# BPBE_Module.net
KiCad netlist of a schematic drawn in Altium Designer
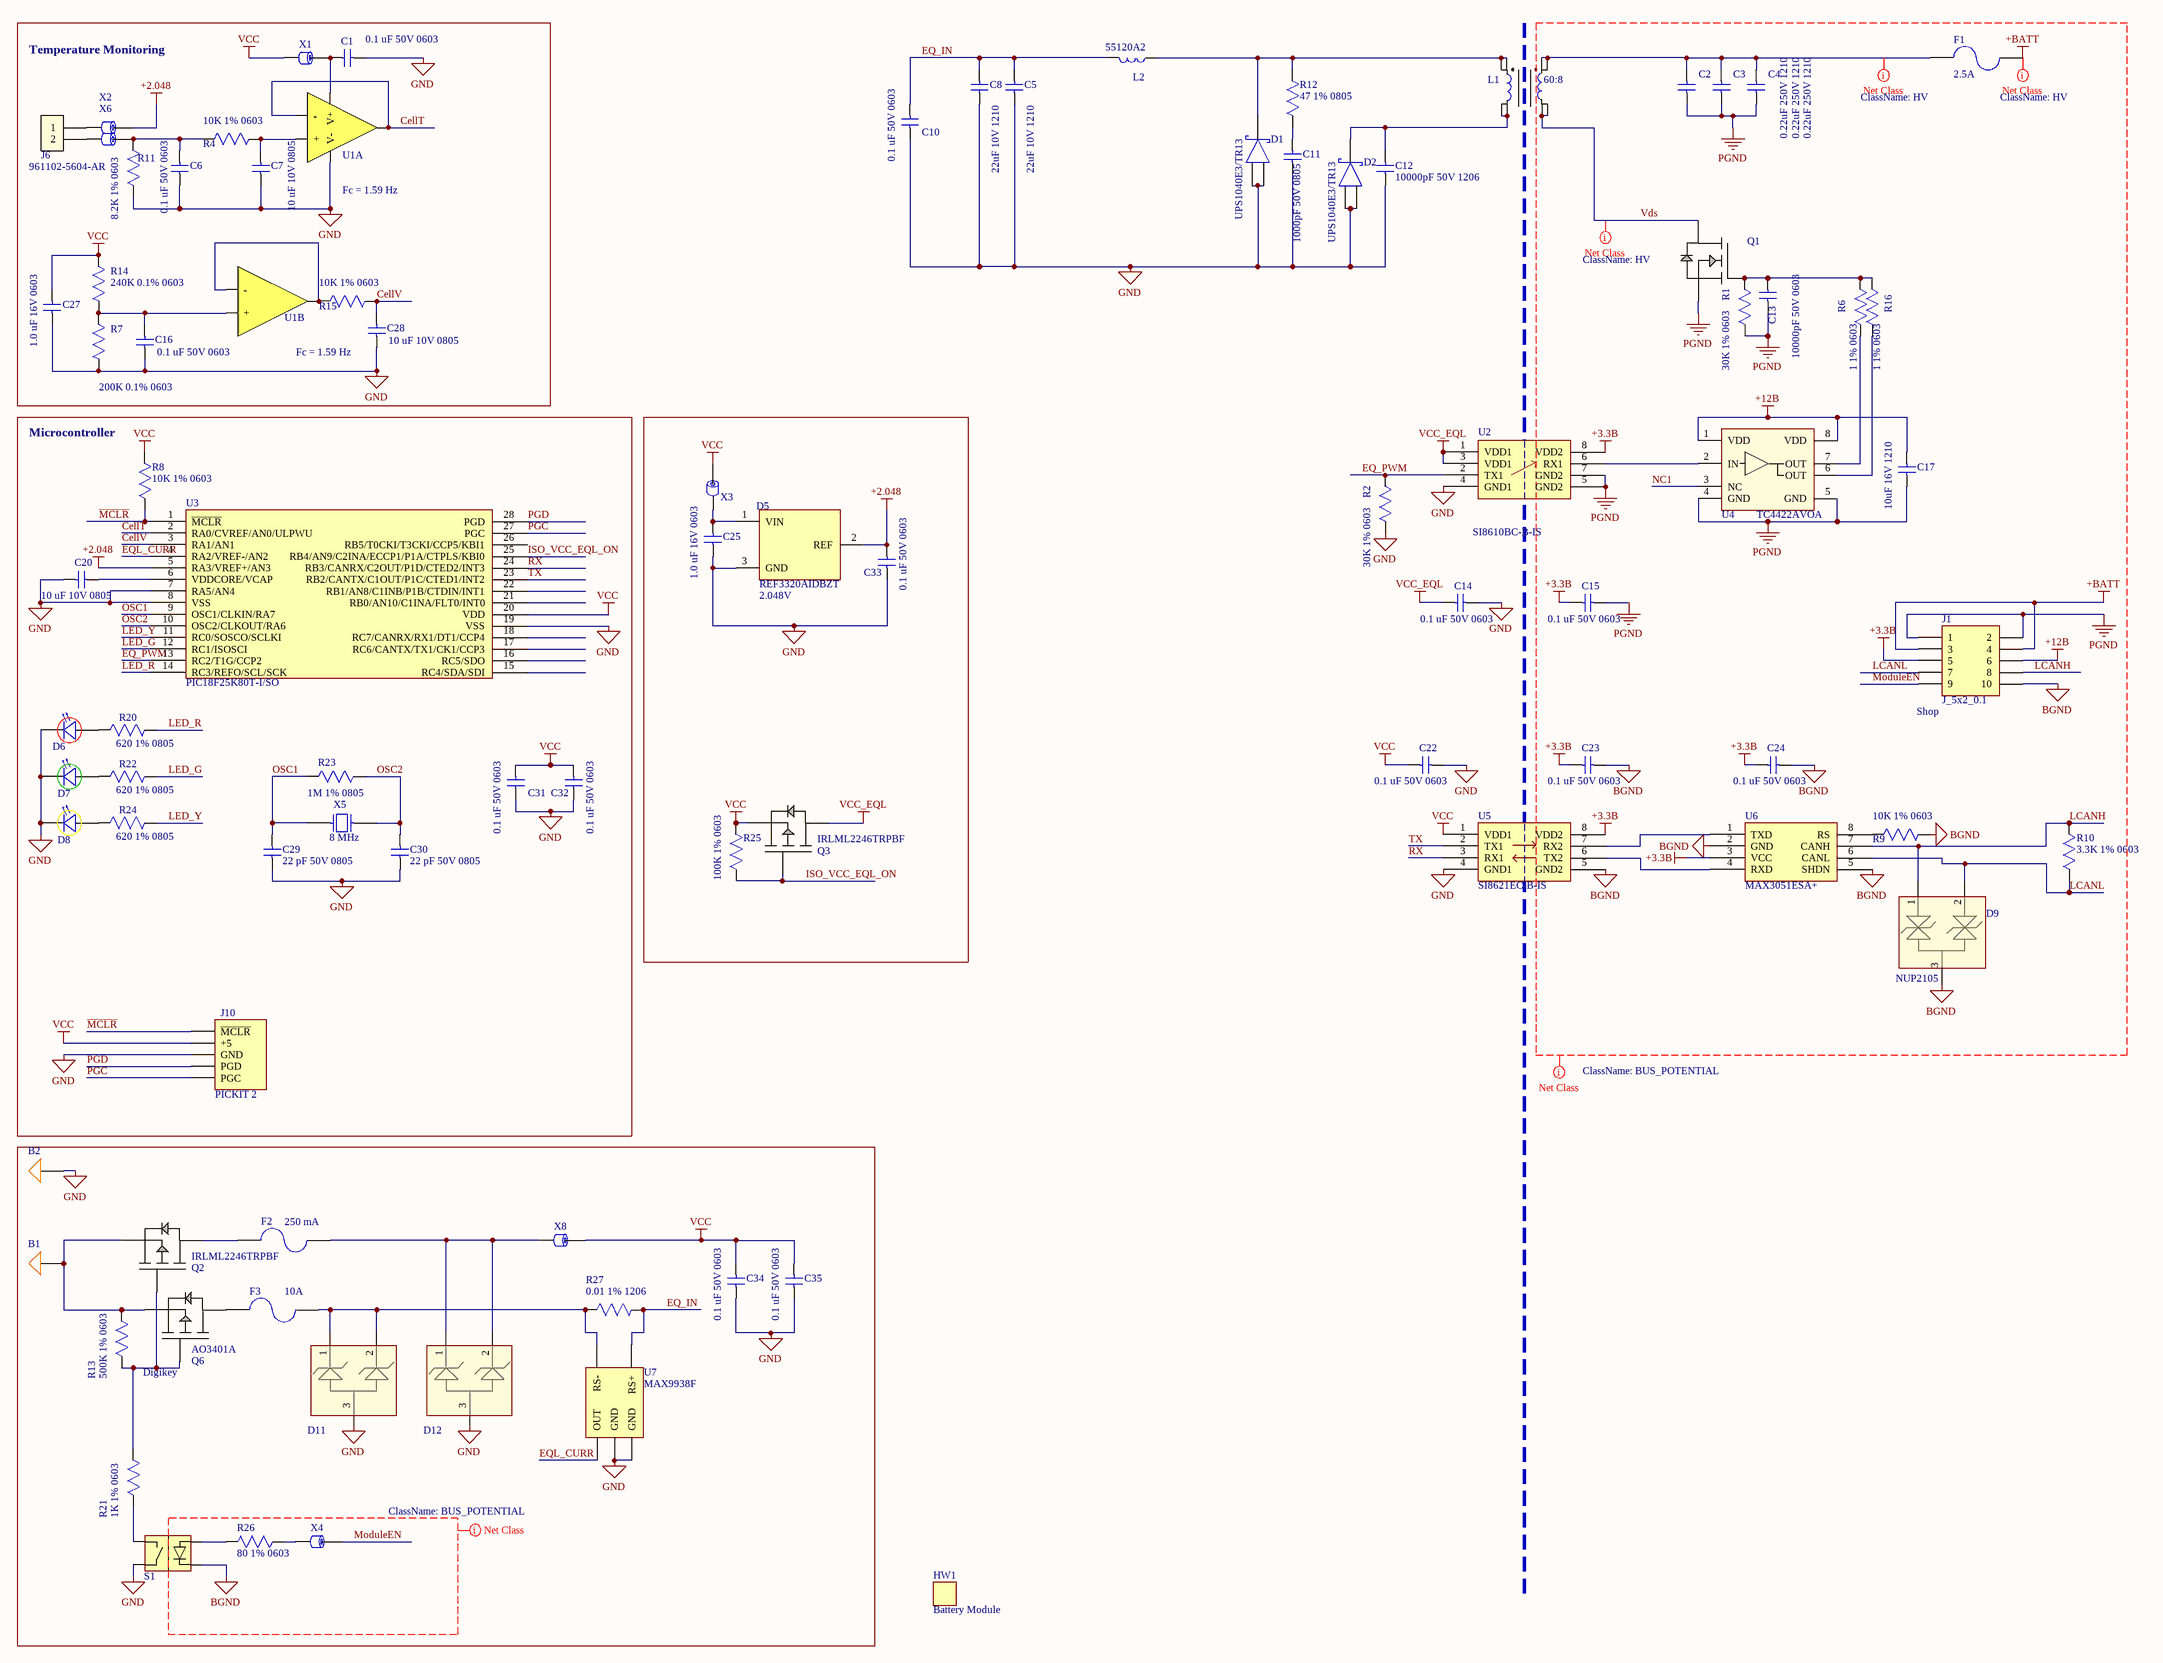
[diagram p0: BPBE Module.SchDoc]

(export (version "E")
  (design (tool "Eeschema 10.0.6"))
  (components
    (comp (ref "B1")
      (value "J_C3_BATTERY_PAD")
      (footprint "BatteryPad")
      (libsource (lib "c3_SchLib") (part "J_C3_BATTERY_PAD"))
    )
    (comp (ref "B2")
      (value "J_C3_BATTERY_PAD")
      (footprint "BatteryPad")
      (libsource (lib "c3_SchLib") (part "J_C3_BATTERY_PAD"))
    )
    (comp (ref "C1")
      (value "0.1 uF 50V 0603")
      (footprint "0603_cap")
      (description "CAP CER 0.1UF 50V 10% X7R 0603")
      (fields (field (name "MANUFACTURER") "Yaego") (field (name "Comment") "CAP 0603"))
      (libsource (lib "Nutz") (part "C_0603"))
    )
    (comp (ref "C2")
      (value "0.22uF 250V 1210")
      (footprint "1210_Capacitor")
      (description "CAP CER 0.22UF 250V 20% X7R 1210")
      (fields (field (name "MANUFACTURER") "TDK Corporation") (field (name "Comment") "CAP 1210"))
      (libsource (lib "c3_SchLib") (part "C_1210"))
    )
    (comp (ref "C3")
      (value "0.22uF 250V 1210")
      (footprint "1210_Capacitor")
      (description "CAP CER 0.22UF 250V 20% X7R 1210")
      (fields (field (name "MANUFACTURER") "TDK Corporation"))
      (libsource (lib "c3_SchLib") (part "C_1210"))
    )
    (comp (ref "C4")
      (value "0.22uF 250V 1210")
      (footprint "1210_Capacitor")
      (description "CAP CER 0.22UF 250V 20% X7R 1210")
      (fields (field (name "MANUFACTURER") "TDK Corporation") (field (name "Comment") "CAP 1210"))
      (libsource (lib "c3_SchLib") (part "C_1210"))
    )
    (comp (ref "C5")
      (value "22uF 10V 1210")
      (footprint "1210_Capacitor")
      (description "CAP CER 22UF 10V 10% X7R 1210")
      (fields (field (name "MANUFACTURER") "TDK Corporation") (field (name "Comment") "CAP 1210"))
      (libsource (lib "c3_SchLib") (part "C_1210"))
    )
    (comp (ref "C6")
      (value "0.1 uF 50V 0603")
      (footprint "0603_cap")
      (description "CAP CER 0.1UF 50V 10% X7R 0603")
      (fields (field (name "MANUFACTURER") "Yaego") (field (name "Comment") "CAP 0603"))
      (libsource (lib "Nutz") (part "C_0603"))
    )
    (comp (ref "C7")
      (value "10 uF 10V 0805")
      (footprint "0805_Capacitor")
      (description "CAP CER 10UF 10V 10% X5R 0805")
      (fields (field (name "MANUFACTURER") "Taiyo Yuden") (field (name "Comment") "CAP 0805"))
      (libsource (lib "Nutz") (part "C_0805"))
    )
    (comp (ref "C8")
      (value "22uF 10V 1210")
      (footprint "1210_Capacitor")
      (description "CAP CER 22UF 10V 10% X7R 1210")
      (fields (field (name "MANUFACTURER") "TDK Corporation") (field (name "Comment") "CAP 1210"))
      (libsource (lib "c3_SchLib") (part "C_1210"))
    )
    (comp (ref "C10")
      (value "0.1 uF 50V 0603")
      (footprint "0603_cap")
      (description "CAP CER 0.1UF 50V 10% X7R 0603")
      (fields (field (name "MANUFACTURER") "Yaego") (field (name "Comment") "CAP 0603"))
      (libsource (lib "Nutz") (part "C_0603"))
    )
    (comp (ref "C11")
      (value "1000pF 50V 0805")
      (footprint "0805_Capacitor")
      (description "CAP CER 1000PF 50V 10% NP0 0805")
      (fields (field (name "MANUFACTURER") "Johanson Dielectrics Inc") (field (name "Comment") "CAP 1000pF"))
      (libsource (lib "c3_SchLib") (part "C_0805_1000pF"))
    )
    (comp (ref "C12")
      (value "10000pF 50V 1206")
      (footprint "1206_CAPACITOR")
      (description "CAP CERM 1206")
      (fields (field (name "Comment") "CAP 1206"))
      (libsource (lib "Nutz") (part "C_1206"))
    )
    (comp (ref "C13")
      (value "10000pF 50V 0603")
      (footprint "0603_cap")
      (description "CAP CER 10000PF 50V 10% X7R 0603")
      (fields (field (name "MANUFACTURER") "Yageo") (field (name "Comment") "CAP 0603"))
      (libsource (lib "Nutz") (part "C_0603"))
    )
    (comp (ref "C14")
      (value "0.1 uF 50V 0603")
      (footprint "0603_cap")
      (description "CAP CER 0.1UF 50V 10% X7R 0603")
      (fields (field (name "MANUFACTURER") "Yaego") (field (name "Comment") "CAP 0603"))
      (libsource (lib "Nutz") (part "C_0603"))
    )
    (comp (ref "C15")
      (value "0.1 uF 50V 0603")
      (footprint "0603_cap")
      (description "CAP CER 0.1UF 50V 10% X7R 0603")
      (fields (field (name "MANUFACTURER") "Yaego") (field (name "Comment") "CAP 0603"))
      (libsource (lib "Nutz") (part "C_0603"))
    )
    (comp (ref "C16")
      (value "0.1 uF 50V 0603")
      (footprint "0603_cap")
      (description "CAP CER 0.1UF 50V 10% X7R 0603")
      (fields (field (name "MANUFACTURER") "Yaego") (field (name "Comment") "CAP 0603"))
      (libsource (lib "Nutz") (part "C_0603"))
    )
    (comp (ref "C17")
      (value "10uF 16V 1210")
      (footprint "1210_Capacitor")
      (description "CAP CER 10UF 16V 10% X5R 1210")
      (fields (field (name "MANUFACTURER") "Taiyo Yuden") (field (name "Comment") "CAP 1210"))
      (libsource (lib "c3_SchLib") (part "C_1210"))
    )
    (comp (ref "C20")
      (value "10 uF 10V 0805")
      (footprint "0805_Capacitor")
      (description "CAP CER 10UF 10V 10% X5R 0805")
      (fields (field (name "MANUFACTURER") "Taiyo Yuden") (field (name "Comment") "CAP 0805"))
      (libsource (lib "Nutz") (part "C_0805"))
    )
    (comp (ref "C22")
      (value "0.1 uF 50V 0603")
      (footprint "0603_cap")
      (description "CAP CER 0.1UF 50V 10% X7R 0603")
      (fields (field (name "MANUFACTURER") "Yaego") (field (name "Comment") "CAP 0603"))
      (libsource (lib "Nutz") (part "C_0603"))
    )
    (comp (ref "C23")
      (value "0.1 uF 50V 0603")
      (footprint "0603_cap")
      (description "CAP CER 0.1UF 50V 10% X7R 0603")
      (fields (field (name "MANUFACTURER") "Yaego") (field (name "Comment") "CAP 0603"))
      (libsource (lib "Nutz") (part "C_0603"))
    )
    (comp (ref "C24")
      (value "0.1 uF 50V 0603")
      (footprint "0603_cap")
      (description "CAP CER 0.1UF 50V 10% X7R 0603")
      (fields (field (name "MANUFACTURER") "Yaego") (field (name "Comment") "CAP 0603"))
      (libsource (lib "Nutz") (part "C_0603"))
    )
    (comp (ref "C25")
      (value "1.0 uF 16V 0603")
      (footprint "0603_cap")
      (description "CAP CER 1UF 16V 10% X7R 0603")
      (fields (field (name "MANUFACTURER") "Taiyo Yuden") (field (name "Comment") "CAP 0603"))
      (libsource (lib "Nutz") (part "C_0603"))
    )
    (comp (ref "C27")
      (value "1.0 uF 16V 0603")
      (footprint "0603_cap")
      (description "CAP CER 1UF 16V 10% X7R 0603")
      (fields (field (name "MANUFACTURER") "Taiyo Yuden") (field (name "Comment") "CAP 0603"))
      (libsource (lib "Nutz") (part "C_0603"))
    )
    (comp (ref "C28")
      (value "10 uF 10V 0805")
      (footprint "0805_Capacitor")
      (description "CAP CER 10UF 10V 10% X5R 0805")
      (fields (field (name "MANUFACTURER") "Taiyo Yuden") (field (name "Comment") "CAP 0805"))
      (libsource (lib "Nutz") (part "C_0805"))
    )
    (comp (ref "C29")
      (value "22 pF 50V 0805")
      (footprint "0805_Capacitor")
      (description "CAP CER 22PF 50V 5% NP0 0805")
      (fields (field (name "MANUFACTURER") "Johanson Dielectrics Inc") (field (name "Comment") "CAP 0805"))
      (libsource (lib "Nutz") (part "C_0805"))
    )
    (comp (ref "C30")
      (value "22 pF 50V 0805")
      (footprint "0805_Capacitor")
      (description "CAP CER 22PF 50V 5% NP0 0805")
      (fields (field (name "MANUFACTURER") "Johanson Dielectrics Inc") (field (name "Comment") "CAP 0805"))
      (libsource (lib "Nutz") (part "C_0805"))
    )
    (comp (ref "C31")
      (value "0.1 uF 50V 0603")
      (footprint "0603_cap")
      (description "CAP CER 0.1UF 50V 10% X7R 0603")
      (fields (field (name "MANUFACTURER") "Yaego") (field (name "Comment") "CAP 0603"))
      (libsource (lib "Nutz") (part "C_0603"))
    )
    (comp (ref "C32")
      (value "0.1 uF 50V 0603")
      (footprint "0603_cap")
      (description "CAP CER 0.1UF 50V 10% X7R 0603")
      (fields (field (name "MANUFACTURER") "Yaego") (field (name "Comment") "CAP 0603"))
      (libsource (lib "Nutz") (part "C_0603"))
    )
    (comp (ref "C33")
      (value "0.1 uF 50V 0603")
      (footprint "0603_cap")
      (description "CAP CER 0.1UF 50V 10% X7R 0603")
      (fields (field (name "MANUFACTURER") "Yaego") (field (name "Comment") "CAP 0603"))
      (libsource (lib "Nutz") (part "C_0603"))
    )
    (comp (ref "C34")
      (value "0.1 uF 50V 0603")
      (footprint "0603_cap")
      (description "CAP CER 0.1UF 50V 10% X7R 0603")
      (fields (field (name "MANUFACTURER") "Yaego") (field (name "Comment") "CAP 0603"))
      (libsource (lib "Nutz") (part "C_0603"))
    )
    (comp (ref "C35")
      (value "0.1 uF 50V 0603")
      (footprint "0603_cap")
      (description "CAP CER 0.1UF 50V 10% X7R 0603")
      (fields (field (name "MANUFACTURER") "Yaego") (field (name "Comment") "CAP 0603"))
      (libsource (lib "Nutz") (part "C_0603"))
    )
    (comp (ref "D1")
      (value "UPS1040E3/TR13")
      (footprint "TO-277")
      (description "DIODE SCHOTTKY 10A 40V PWRMITE3")
      (fields (field (name "MANUFACTURER") "Microsemi") (field (name "MANUFACTURER PN") "UPS1040E3/TR13"))
      (libsource (lib "c3_SchLib") (part "D_UPS1040E3/TR13"))
    )
    (comp (ref "D2")
      (value "UPS1040E3/TR13")
      (footprint "TO-277")
      (description "DIODE SCHOTTKY 10A 40V PWRMITE3")
      (fields (field (name "MANUFACTURER") "Microsemi") (field (name "MANUFACTURER PN") "UPS1040E3/TR13"))
      (libsource (lib "c3_SchLib") (part "D_UPS1040E3/TR13"))
    )
    (comp (ref "D5")
      (value "2.048V")
      (footprint "SOT-23")
      (description "IC LDO V-REF 2.048V SOT23-3")
      (fields (field (name "MANUFACTURER") "TI") (field (name "MANUFACTURER PN") "REF3320AIDBZT"))
      (libsource (lib "c3_SchLib") (part "D_REF3320AIDBZT"))
    )
    (comp (ref "D6")
      (value "D_LED_0805_RED")
      (footprint "0805P_RED")
      (description "LED 2X1.2MM 625NM RD WTR CLR SMD 0805")
      (fields (field (name "MANUFACTURER") "Kingbright Corp"))
      (libsource (lib "c3_SchLib") (part "D_LED_0805_RED"))
    )
    (comp (ref "D7")
      (value "D_LED_0805_GREEN")
      (footprint "0805P_Green")
      (description "LED 2X1.2MM 568NM GN WTR CLR SMD 0805")
      (fields (field (name "MANUFACTURER") "Kingbright Corp"))
      (libsource (lib "c3_SchLib") (part "D_LED_0805_GREEN"))
    )
    (comp (ref "D8")
      (value "D_LED_0805_YELLOW")
      (footprint "0805P_YELLOW")
      (description "LED 2X1.2MM 588NM YW WTR CLR SMD 0805")
      (fields (field (name "MANUFACTURER") "Kingbright Corp"))
      (libsource (lib "c3_SchLib") (part "D_LED_0805_YELLOW"))
    )
    (comp (ref "D9")
      (value "CAN TVS")
      (footprint "SOT-23")
      (description "IC CAN BUS PROTECTOR DUAL SOT23")
      (fields (field (name "MANUFACTURER") "ON Semiconductor") (field (name "MANUFACTURER PN") "NUP2105"))
      (libsource (lib "c3_SchLib") (part "D_NUP2105"))
    )
    (comp (ref "D11")
      (value "MMBZ6V8AL,215")
      (footprint "SOT-23")
      (description "DIODE ESD PROT DBL 4.5V SOT23")
      (fields (field (name "MANUFACTURER") "NXP"))
      (libsource (lib "c3_SchLib") (part "D_MMBZ6V8AL,215"))
    )
    (comp (ref "D12")
      (value "MMBZ6V8AL,215")
      (footprint "SOT-23")
      (description "DIODE ESD PROT DBL 4.5V SOT23")
      (fields (field (name "MANUFACTURER") "NXP"))
      (libsource (lib "c3_SchLib") (part "D_MMBZ6V8AL,215"))
    )
    (comp (ref "F1")
      (value "2.5A")
      (footprint "2410")
      (description "FUSE 2.5A 125V FAST 2410")
      (fields (field (name "MANUFACTURER") "TE Connectivity") (field (name "Comment") "F_SSQ 12"))
      (libsource (lib "c3_SchLib") (part "F_SSQ 12"))
    )
    (comp (ref "F2")
      (value "250 mA")
      (footprint "1206_RESISTOR")
      (description "FUSE 250MA 125V 1206 FAST C1Q")
      (fields (field (name "MANUFACTURER") "Bel Fuse Inc"))
      (libsource (lib "c3_SchLib") (part "F_250mA_1206"))
    )
    (comp (ref "F3")
      (value "10A")
      (footprint "2410")
      (description "FUSE 10A 125V 6125 FAST SSQ")
      (fields (field (name "MANUFACTURER") "Bel Fuse Inc") (field (name "Comment") "F_SSQ 10"))
      (libsource (lib "c3_SchLib") (part "F_SSQ 12"))
    )
    (comp (ref "HW1")
      (value "Battery Module")
      (footprint "Battery Module")
      (libsource (lib "c3_SchLib") (part "Battery Module"))
    )
    (comp (ref "J1")
      (value "J_5x2_0.1")
      (footprint "10PIN_2_.100IN")
      (description "5 x 2 0.1\" Header")
      (fields (field (name "DISTRIBUTOR") "Shop"))
      (libsource (lib "Nutz") (part "J_5x2_0.1"))
    )
    (comp (ref "J6")
      (value "J_Thermistor_Connector")
      (footprint "SIP_HEADER_2")
      (description "Thermistor Connector")
      (fields (field (name "MANUFACTURER PN") "961102-5604-AR") (field (name "MANUFACTURER") "3M"))
      (libsource (lib "c3_SchLib") (part "J_Thermistor_Connector"))
    )
    (comp (ref "J10")
      (value "PICKIT 2")
      (footprint "CONN FEMALE 5POS .100\" R/A GOLD")
      (description "PICKIT2 PROG HEADER")
      (fields
        (field (name "MANUFACTURER") "Sullins Connector Solutions")
        (field (name "Comment") "J_PICKIT2_5")
      )
      (libsource (lib "c3_SchLib") (part "J_PICKIT2_5"))
    )
    (comp (ref "L1")
      (value "60:8")
      (footprint "PCB1808B1")
      (description "10:1 Custom Transformer")
      (fields (field (name "MANUFACTURER") "Magnetics, Inc.") (field (name "Comment") "L_PCB1808B1"))
      (libsource (lib "c3_SchLib") (part "L_PCB1808B1"))
    )
    (comp (ref "L2")
      (value "L_MagInc_55120A2")
      (footprint "Magnetics_55120A2")
      (description "55120A2")
      (fields (field (name "MANUFACTURER") "Magnetics Inc") (field (name "MANUFACTURER PN") "55120A2"))
      (libsource (lib "c3_SchLib") (part "L_MagInc_55120A2"))
    )
    (comp (ref "Q1")
      (value "IPD600N25N3 G")
      (footprint "DPAK - JN")
      (description "MOSFET N-CH 250V 25A TO252-3")
      (fields (field (name "MANUFACTURER") "Infineon"))
      (libsource (lib "c3_SchLib") (part "Q_IPD600N25N3 G"))
    )
    (comp (ref "Q2")
      (value "IRLML2246TRPBF")
      (footprint "SOT-23")
      (description "MOSFET P-CH 20V 2.6A SOT23")
      (fields (field (name "MANUFACTURER") "International Rectifier"))
      (libsource (lib "c3_SchLib") (part "Q_FDN302P"))
    )
    (comp (ref "Q3")
      (value "IRLML2246TRPBF")
      (footprint "SOT-23")
      (description "MOSFET P-CH 20V 2.6A SOT23")
      (fields (field (name "MANUFACTURER") "International Rectifier"))
      (libsource (lib "c3_SchLib") (part "Q_FDN302P"))
    )
    (comp (ref "Q6")
      (value "Q_AO3401A")
      (footprint "SOT-23")
      (description "MOSFET P-CH -30V -4.3A SOT23")
      (fields
        (field (name "MANUFACTURER") "Alpha & Omega")
        (field (name "MANUFACTURER PN") "AO3401A")
        (field (name "DISTRIBUTOR") "Digikey")
      )
      (libsource (lib "Nutz") (part "Q_AO3401A"))
    )
    (comp (ref "R1")
      (value "30K 1% 0603")
      (footprint "0603_res")
      (description "RESISTOR, 1/10W, 30K, 1%, 0603")
      (fields (field (name "MANUFACTURER") "ANY / EQUIV") (field (name "Comment") "RES 0603"))
      (libsource (lib "Nutz") (part "R_0603"))
    )
    (comp (ref "R2")
      (value "30K 1% 0603")
      (footprint "0603_res")
      (description "RESISTOR, 1/10W, 30K, 1%, 0603")
      (fields (field (name "MANUFACTURER") "ANY / EQUIV") (field (name "Comment") "RES 0603"))
      (libsource (lib "Nutz") (part "R_0603"))
    )
    (comp (ref "R4")
      (value "10K 1% 0603")
      (footprint "0603_res")
      (description "RESISTOR, 1/10W, 10K, 1%, 0603")
      (fields (field (name "MANUFACTURER") "ANY / EQUIV") (field (name "Comment") "RES 0603"))
      (libsource (lib "Nutz") (part "R_0603"))
    )
    (comp (ref "R6")
      (value "1 1% 0603")
      (footprint "0603_res")
      (description "RESISTOR, 1/10W, 1, 1%, 0603")
      (fields (field (name "MANUFACTURER") "ANY / EQUIV") (field (name "Comment") "RES 0603"))
      (libsource (lib "Nutz") (part "R_0603"))
    )
    (comp (ref "R7")
      (value "200K 0.1% 0603")
      (footprint "0603_res")
      (description "RESISTOR, 1/10W, 200K, 0.1%, 0603")
      (fields (field (name "MANUFACTURER") "ANY / EQUIV") (field (name "Comment") "RES 0603"))
      (libsource (lib "Nutz") (part "R_0603"))
    )
    (comp (ref "R8")
      (value "10K 1% 0603")
      (footprint "0603_res")
      (description "RESISTOR, 1/10W, 10K, 1%, 0603")
      (fields (field (name "MANUFACTURER") "ANY / EQUIV") (field (name "Comment") "RES 0603"))
      (libsource (lib "Nutz") (part "R_0603"))
    )
    (comp (ref "R9")
      (value "10K 1% 0603")
      (footprint "0603_res")
      (description "RESISTOR, 1/10W, 10K, 1%, 0603")
      (fields (field (name "MANUFACTURER") "ANY / EQUIV") (field (name "Comment") "RES 0603"))
      (libsource (lib "Nutz") (part "R_0603"))
    )
    (comp (ref "R10")
      (value "3.3K 1% 0603")
      (footprint "0603_res")
      (description "RESISTOR, 1/10W, 3.3K, 1%, 0603")
      (fields (field (name "MANUFACTURER") "ANY / EQUIV") (field (name "Comment") "RES 0603"))
      (libsource (lib "Nutz") (part "R_0603"))
    )
    (comp (ref "R11")
      (value "8.2K 1% 0603")
      (footprint "0603_res")
      (description "RESISTOR, 1/10W, 8.2K, 1%, 0603")
      (fields (field (name "MANUFACTURER") "ANY / EQUIV") (field (name "Comment") "RES 0603"))
      (libsource (lib "Nutz") (part "R_0603"))
    )
    (comp (ref "R12")
      (value "47 1% 0805")
      (footprint "0805_Resistor")
      (description "RESISTOR, 1/8W, 47, 1%, 0805")
      (fields (field (name "MANUFACTURER") "ANY / EQUIV") (field (name "Comment") "RES 0805"))
      (libsource (lib "Nutz") (part "R_0805"))
    )
    (comp (ref "R13")
      (value "500K 1% 0603")
      (footprint "0603_res")
      (description "RESISTOR, 1/10W, 500K, 1%, 0603")
      (fields (field (name "MANUFACTURER") "ANY / EQUIV") (field (name "Comment") "RES 0603"))
      (libsource (lib "Nutz") (part "R_0603"))
    )
    (comp (ref "R14")
      (value "240K 0.1% 0603")
      (footprint "0603_res")
      (description "RESISTOR, 1/10W, 240K, 0.1%, 0603")
      (fields (field (name "MANUFACTURER") "ANY / EQUIV") (field (name "Comment") "RES 0603"))
      (libsource (lib "Nutz") (part "R_0603"))
    )
    (comp (ref "R15")
      (value "10K 1% 0603")
      (footprint "0603_res")
      (description "RESISTOR, 1/10W, 10K, 1%, 0603")
      (fields (field (name "MANUFACTURER") "ANY / EQUIV") (field (name "Comment") "RES 0603"))
      (libsource (lib "Nutz") (part "R_0603"))
    )
    (comp (ref "R16")
      (value "1 1% 0603")
      (footprint "0603_res")
      (description "RESISTOR, 1/10W, 1, 1%, 0603")
      (fields (field (name "MANUFACTURER") "ANY / EQUIV") (field (name "Comment") "RES 0603"))
      (libsource (lib "Nutz") (part "R_0603"))
    )
    (comp (ref "R20")
      (value "620 1% 0805")
      (footprint "0805_Resistor")
      (description "RESISTOR, 1/8W, 620, 1%, 0805")
      (fields (field (name "MANUFACTURER") "ANY / EQUIV") (field (name "Comment") "R_0805_620_1%"))
      (libsource (lib "c3_SchLib") (part "R_0805_620_1%"))
    )
    (comp (ref "R21")
      (value "1K 1% 0603")
      (footprint "0603_res")
      (description "RESISTOR, 1/10W, 1K, 1%, 0603")
      (fields (field (name "MANUFACTURER") "ANY / EQUIV") (field (name "Comment") "RES 0603"))
      (libsource (lib "Nutz") (part "R_0603"))
    )
    (comp (ref "R22")
      (value "620 1% 0805")
      (footprint "0805_Resistor")
      (description "RESISTOR, 1/8W, 620, 1%, 0805")
      (fields (field (name "MANUFACTURER") "ANY / EQUIV") (field (name "Comment") "R_0805_620_1%"))
      (libsource (lib "c3_SchLib") (part "R_0805_620_1%"))
    )
    (comp (ref "R23")
      (value "1M 1% 0805")
      (footprint "0805_Resistor")
      (description "RESISTOR, 1/8W, 1M, 1%, 0805")
      (fields (field (name "MANUFACTURER") "ANY / EQUIV") (field (name "Comment") "RES 0805"))
      (libsource (lib "Nutz") (part "R_0805"))
    )
    (comp (ref "R24")
      (value "620 1% 0805")
      (footprint "0805_Resistor")
      (description "RESISTOR, 1/8W, 620, 1%, 0805")
      (fields (field (name "MANUFACTURER") "ANY / EQUIV") (field (name "Comment") "R_0805_620_1%"))
      (libsource (lib "c3_SchLib") (part "R_0805_620_1%"))
    )
    (comp (ref "R25")
      (value "100K 1% 0603")
      (footprint "0603_res")
      (description "RESISTOR, 1/10W, 100K, 1%, 0603")
      (fields (field (name "MANUFACTURER") "ANY / EQUIV") (field (name "Comment") "RES 0603"))
      (libsource (lib "Nutz") (part "R_0603"))
    )
    (comp (ref "R26")
      (value "80 1% 0603")
      (footprint "0603_res")
      (description "RESISTOR, 1/10W, 80, 1%, 0603")
      (fields (field (name "MANUFACTURER") "ANY / EQUIV") (field (name "Comment") "RES 0603"))
      (libsource (lib "Nutz") (part "R_0603"))
    )
    (comp (ref "R27")
      (value "0.01 1% 1206")
      (footprint "1206_Resistor")
      (description "RES CURRENT SENSE .010 OHM 1W 1%")
      (fields (field (name "MANUFACTURER") "MCS1632R010FER") (field (name "Comment") "R_0805_0.01_1%"))
      (libsource (lib "c3_SchLib") (part "R_0805_0.01_1%"))
    )
    (comp (ref "S1")
      (value "CPC1017NTR")
      (footprint "CPC1017NTR")
      (description "PHOTOCPLR RELAY MOSFET-OUT 4-SOP")
      (fields (field (name "MANUFACTURER") "Clare"))
      (libsource (lib "c3_SchLib") (part "U_CPC1017NTR"))
    )
    (comp (ref "U1")
      (value "IC OP AMP")
      (footprint "SOIC127P600X175-8N")
      (description "IC OPAMP 1UA 1.4V DUAL R-R 8SOIC")
      (fields (field (name "MANUFACTURER") "Microchip") (field (name "SVP CREATOR") "Jonathan Nutzmann"))
      (libsource (lib "c3_SchLib") (part "U_MCP6042T-I/SN"))
    )
    (comp (ref "U2")
      (value "U_SI8610EC")
      (footprint "SOIC127P600X175-8N")
      (description "IC ISOLATOR 1CH 3.75KV 8-SOIC")
      (fields (field (name "MANUFACTURER") "Silicon Labs") (field (name "MANUFACTURER PN") "SI8610BC-B-IS"))
      (libsource (lib "c3_SchLib") (part "U_SI8610EC"))
    )
    (comp (ref "U3")
      (value "PIC18F25K80")
      (footprint "SOIC127P1030X265-28N")
      (description "MCU PIC 32KB FLASH 28SOIC")
      (fields (field (name "MANUFACTURER") "Microchip") (field (name "MANUFACTURER PN") "PIC18F25K80T-I/SO"))
      (libsource (lib "c3_SchLib") (part "U_PIC18F25K80"))
    )
    (comp (ref "U4")
      (value "TC4422AVOA")
      (footprint "SOIC127P600X175-8N")
      (description "IC MOSFET DVR 9A NON-INV 8SOIC")
      (fields (field (name "MANUFACTURER") "Microchip") (field (name "MANUFACTURER PN") "TC4422AVOA"))
      (libsource (lib "c3_SchLib") (part "U_TC4422AVOA"))
    )
    (comp (ref "U5")
      (value "U_SI8621EC")
      (footprint "SOIC127P600X175-8N")
      (description "IC ISOLATOR 2CH 3.75KV 8SOIC")
      (fields (field (name "MANUFACTURER") "Silicon Labs") (field (name "MANUFACTURER PN") "SI8621EC-B-IS"))
      (libsource (lib "c3_SchLib") (part "U_SI8621EC"))
    )
    (comp (ref "U6")
      (value "U_MAX3051")
      (footprint "SOIC127P600X175-8N")
      (description "IC TXRX CAN 1MBPS 8-SOIC 3.3V")
      (fields (field (name "MANUFACTURER") "Maxim") (field (name "MANUFACTURER PN") "MAX3051ESA+"))
      (libsource (lib "c3_SchLib") (part "U_MAX3051"))
    )
    (comp (ref "U7")
      (value "MAX9938F")
      (footprint "SOT95P280X145-5N")
      (description "IC AMP CURRENT SENSE SOT23-5")
      (fields (field (name "MANUFACTURER") "Maxim") (field (name "Comment") "U_ MAX9938F"))
      (libsource (lib "c3_SchLib") (part "U_ MAX9938F"))
    )
    (comp (ref "X1")
      (value "0603")
      (footprint "0603_res")
      (description "FERRITE CHIP 2A 300 OHM SMD")
      (fields (field (name "MANUFACTURER") "Laird-Signal Integrity Products"))
      (libsource (lib "Nutz") (part "X_0603_FERRITE"))
    )
    (comp (ref "X2")
      (value "0603")
      (footprint "0603_res")
      (description "FERRITE CHIP 2A 300 OHM SMD")
      (fields (field (name "MANUFACTURER") "Laird-Signal Integrity Products"))
      (libsource (lib "Nutz") (part "X_0603_FERRITE"))
    )
    (comp (ref "X3")
      (value "0603")
      (footprint "0603_res")
      (description "FERRITE CHIP 2A 300 OHM SMD")
      (fields (field (name "MANUFACTURER") "Laird-Signal Integrity Products"))
      (libsource (lib "") (part "X_0603_FERRITE_1"))
    )
    (comp (ref "X4")
      (value "0603")
      (footprint "0603_res")
      (description "FERRITE CHIP 2A 300 OHM SMD")
      (fields (field (name "MANUFACTURER") "Laird-Signal Integrity Products"))
      (libsource (lib "Nutz") (part "X_0603_FERRITE"))
    )
    (comp (ref "X5")
      (value "8 MHz")
      (footprint "HC-49")
      (description "CRYSTAL 8.00 MHZ 20PF 49US")
      (fields (field (name "MANUFACTURER") "ECS") (field (name "Comment") "HC49"))
      (libsource (lib "c3_SchLib") (part "X_HC49"))
    )
    (comp (ref "X6")
      (value "0603")
      (footprint "0603_res")
      (description "FERRITE CHIP 2A 300 OHM SMD")
      (fields (field (name "MANUFACTURER") "Laird-Signal Integrity Products"))
      (libsource (lib "Nutz") (part "X_0603_FERRITE"))
    )
    (comp (ref "X8")
      (value "0603")
      (footprint "0603_res")
      (description "FERRITE CHIP 2A 300 OHM SMD")
      (fields (field (name "MANUFACTURER") "Laird-Signal Integrity Products"))
      (libsource (lib "Nutz") (part "X_0603_FERRITE"))
    )
  )
  (nets
    (net (code "1") (name "+2.048") (class "Default")
      (node (ref "C33") (pin "1") (pinfunction "1_1") (pintype "passive"))
      (node (ref "D5") (pin "2") (pinfunction "REF_2") (pintype "passive"))
      (node (ref "U3") (pin "5") (pinfunction "RA3/VREF+/AN3_5") (pintype "passive"))
      (node (ref "X2") (pin "2") (pinfunction "2_2") (pintype "passive"))
    )
    (net (code "2") (name "+3.3B") (class "Default")
      (node (ref "C15") (pin "1") (pinfunction "1_1") (pintype "passive"))
      (node (ref "C23") (pin "1") (pinfunction "1_1") (pintype "passive"))
      (node (ref "C24") (pin "1") (pinfunction "1_1") (pintype "passive"))
      (node (ref "J1") (pin "5") (pinfunction "5_5") (pintype "passive"))
      (node (ref "U2") (pin "8") (pinfunction "VDD2_8") (pintype "passive"))
      (node (ref "U5") (pin "8") (pinfunction "VDD2_8") (pintype "passive"))
      (node (ref "U6") (pin "3") (pinfunction "VCC_3") (pintype "passive"))
    )
    (net (code "3") (name "+12B") (class "Default")
      (node (ref "C17") (pin "1") (pinfunction "1_1") (pintype "passive"))
      (node (ref "J1") (pin "6") (pinfunction "6_6") (pintype "passive"))
      (node (ref "U4") (pin "1") (pinfunction "VDD_1") (pintype "passive"))
      (node (ref "U4") (pin "8") (pinfunction "VDD_8") (pintype "passive"))
    )
    (net (code "4") (name "+BATT") (class "Default")
      (node (ref "F1") (pin "1") (pinfunction "1_1") (pintype "passive"))
      (node (ref "J1") (pin "3") (pinfunction "3_3") (pintype "passive"))
      (node (ref "J1") (pin "4") (pinfunction "4_4") (pintype "passive"))
    )
    (net (code "5") (name "/CellT") (class "Default")
      (node (ref "U1") (pin "1") (pinfunction "Vo_1") (pintype "passive"))
      (node (ref "U1") (pin "2") (pinfunction "-_2") (pintype "passive"))
      (node (ref "U3") (pin "2") (pinfunction "RA0/CVREF/AN0/ULPWU_2") (pintype "passive"))
    )
    (net (code "6") (name "/CellV") (class "Default")
      (node (ref "C28") (pin "1") (pinfunction "1_1") (pintype "passive"))
      (node (ref "R15") (pin "1") (pinfunction "1_1") (pintype "passive"))
      (node (ref "U3") (pin "3") (pinfunction "RA1/AN1_3") (pintype "passive"))
    )
    (net (code "7") (name "/EQL_CURR") (class "Default")
      (node (ref "U3") (pin "4") (pinfunction "RA2/VREF-/AN2_4") (pintype "passive"))
      (node (ref "U7") (pin "3") (pinfunction "OUT_3") (pintype "passive"))
    )
    (net (code "8") (name "/EQ_IN") (class "Default")
      (node (ref "C10") (pin "1") (pinfunction "1_1") (pintype "passive"))
      (node (ref "C5") (pin "1") (pinfunction "1_1") (pintype "passive"))
      (node (ref "C8") (pin "1") (pinfunction "1_1") (pintype "passive"))
      (node (ref "L2") (pin "2") (pinfunction "2_2") (pintype "passive"))
      (node (ref "R27") (pin "1") (pinfunction "1_1") (pintype "passive"))
      (node (ref "U7") (pin "5") (pinfunction "RS+_5") (pintype "passive"))
    )
    (net (code "9") (name "/EQ_PWM") (class "Default")
      (node (ref "R2") (pin "1") (pinfunction "1_1") (pintype "passive"))
      (node (ref "U2") (pin "2") (pinfunction "TX1_2") (pintype "passive"))
      (node (ref "U3") (pin "13") (pinfunction "RC2/T1G/CCP2_13") (pintype "passive"))
    )
    (net (code "10") (name "/ISO_VCC_EQL_ON") (class "Default")
      (node (ref "Q3") (pin "1") (pinfunction "GATE_1") (pintype "passive"))
      (node (ref "R25") (pin "2") (pinfunction "2_2") (pintype "passive"))
      (node (ref "U3") (pin "25") (pinfunction "RB4/AN9/C2INA/ECCP1/P1A/CTPLS/KBI0_25") (pintype "passive"))
    )
    (net (code "11") (name "/LCANH") (class "Default")
      (node (ref "D9") (pin "1") (pintype "passive"))
      (node (ref "J1") (pin "8") (pinfunction "8_8") (pintype "passive"))
      (node (ref "R10") (pin "1") (pinfunction "1_1") (pintype "passive"))
      (node (ref "U6") (pin "7") (pinfunction "CANH_7") (pintype "passive"))
    )
    (net (code "12") (name "/LCANL") (class "Default")
      (node (ref "D9") (pin "2") (pintype "passive"))
      (node (ref "J1") (pin "7") (pinfunction "7_7") (pintype "passive"))
      (node (ref "R10") (pin "2") (pinfunction "2_2") (pintype "passive"))
      (node (ref "U6") (pin "6") (pinfunction "CANL_6") (pintype "passive"))
    )
    (net (code "13") (name "/LED_G") (class "Default")
      (node (ref "R22") (pin "1") (pinfunction "1_1") (pintype "passive"))
      (node (ref "U3") (pin "12") (pinfunction "RC1/ISOSCI_12") (pintype "passive"))
    )
    (net (code "14") (name "/LED_R") (class "Default")
      (node (ref "R20") (pin "1") (pinfunction "1_1") (pintype "passive"))
      (node (ref "U3") (pin "14") (pinfunction "RC3/REFO/SCL/SCK_14") (pintype "passive"))
    )
    (net (code "15") (name "/LED_Y") (class "Default")
      (node (ref "R24") (pin "1") (pinfunction "1_1") (pintype "passive"))
      (node (ref "U3") (pin "11") (pinfunction "RC0/SOSCO/SCLKI_11") (pintype "passive"))
    )
    (net (code "16") (name "/ModuleEN") (class "Default")
      (node (ref "J1") (pin "9") (pinfunction "9_9") (pintype "passive"))
      (node (ref "X4") (pin "2") (pinfunction "2_2") (pintype "passive"))
    )
    (net (code "17") (name "/NC1") (class "Default")
      (node (ref "U4") (pin "3") (pinfunction "NC_3") (pintype "passive"))
    )
    (net (code "18") (name "/OSC1") (class "Default")
      (node (ref "C29") (pin "1") (pinfunction "1_1") (pintype "passive"))
      (node (ref "R23") (pin "2") (pinfunction "2_2") (pintype "passive"))
      (node (ref "U3") (pin "9") (pinfunction "OSC1/CLKIN/RA7_9") (pintype "passive"))
      (node (ref "X5") (pin "2") (pinfunction "2_2") (pintype "passive"))
    )
    (net (code "19") (name "/OSC2") (class "Default")
      (node (ref "C30") (pin "1") (pinfunction "1_1") (pintype "passive"))
      (node (ref "R23") (pin "1") (pinfunction "1_1") (pintype "passive"))
      (node (ref "U3") (pin "10") (pinfunction "OSC2/CLKOUT/RA6_10") (pintype "passive"))
      (node (ref "X5") (pin "1") (pinfunction "1_1") (pintype "passive"))
    )
    (net (code "20") (name "/PGC") (class "Default")
      (node (ref "J10") (pin "PGC") (pinfunction "PGC_PGC") (pintype "passive"))
      (node (ref "U3") (pin "27") (pinfunction "PGC_27") (pintype "passive"))
    )
    (net (code "21") (name "/PGD") (class "Default")
      (node (ref "J10") (pin "PGD") (pinfunction "PGD_PGD") (pintype "passive"))
      (node (ref "U3") (pin "28") (pinfunction "PGD_28") (pintype "passive"))
    )
    (net (code "22") (name "/RX") (class "Default")
      (node (ref "U3") (pin "24") (pinfunction "RB3/CANRX/C2OUT/P1D/CTED2/INT3_24") (pintype "passive"))
      (node (ref "U5") (pin "3") (pinfunction "RX1_3") (pintype "passive"))
    )
    (net (code "23") (name "/TX") (class "Default")
      (node (ref "U3") (pin "23") (pinfunction "RB2/CANTX/C1OUT/P1C/CTED1/INT2_23") (pintype "passive"))
      (node (ref "U5") (pin "2") (pinfunction "TX1_2") (pintype "passive"))
    )
    (net (code "24") (name "/Vds") (class "Default")
      (node (ref "L1") (pin "7") (pinfunction "7_7") (pintype "passive"))
      (node (ref "L1") (pin "8") (pinfunction "8_8") (pintype "passive"))
      (node (ref "Q1") (pin "2") (pinfunction "DRAIN_2") (pintype "passive"))
    )
    (net (code "25") (name "/~{MCLR}") (class "Default")
      (node (ref "J10") (pin "RST") (pinfunction "~{MCLR}_RST") (pintype "passive"))
      (node (ref "R8") (pin "2") (pinfunction "2_2") (pintype "passive"))
      (node (ref "U3") (pin "1") (pinfunction "~{MCLR}_1") (pintype "passive"))
    )
    (net (code "26") (name "BGND") (class "Default")
      (node (ref "C23") (pin "2") (pinfunction "2_2") (pintype "passive"))
      (node (ref "C24") (pin "2") (pinfunction "2_2") (pintype "passive"))
      (node (ref "D9") (pin "3") (pintype "passive"))
      (node (ref "J1") (pin "10") (pinfunction "10_10") (pintype "passive"))
      (node (ref "R9") (pin "1") (pinfunction "1_1") (pintype "passive"))
      (node (ref "S1") (pin "2") (pinfunction "2_2") (pintype "passive"))
      (node (ref "U5") (pin "5") (pinfunction "GND2_5") (pintype "passive"))
      (node (ref "U6") (pin "2") (pinfunction "GND_2") (pintype "passive"))
      (node (ref "U6") (pin "5") (pinfunction "SHDN_5") (pintype "passive"))
    )
    (net (code "27") (name "GND") (class "Default")
      (node (ref "B2") (pin "1") (pinfunction "1_1") (pintype "passive"))
      (node (ref "C1") (pin "2") (pinfunction "2_2") (pintype "passive"))
      (node (ref "C10") (pin "2") (pinfunction "2_2") (pintype "passive"))
      (node (ref "C11") (pin "2") (pinfunction "2_2") (pintype "passive"))
      (node (ref "C12") (pin "2") (pinfunction "2_2") (pintype "passive"))
      (node (ref "C14") (pin "2") (pinfunction "2_2") (pintype "passive"))
      (node (ref "C16") (pin "2") (pinfunction "2_2") (pintype "passive"))
      (node (ref "C20") (pin "2") (pinfunction "2_2") (pintype "passive"))
      (node (ref "C22") (pin "2") (pinfunction "2_2") (pintype "passive"))
      (node (ref "C25") (pin "2") (pinfunction "2_2") (pintype "passive"))
      (node (ref "C27") (pin "2") (pinfunction "2_2") (pintype "passive"))
      (node (ref "C28") (pin "2") (pinfunction "2_2") (pintype "passive"))
      (node (ref "C29") (pin "2") (pinfunction "2_2") (pintype "passive"))
      (node (ref "C30") (pin "2") (pinfunction "2_2") (pintype "passive"))
      (node (ref "C31") (pin "2") (pinfunction "2_2") (pintype "passive"))
      (node (ref "C32") (pin "2") (pinfunction "2_2") (pintype "passive"))
      (node (ref "C33") (pin "2") (pinfunction "2_2") (pintype "passive"))
      (node (ref "C34") (pin "2") (pinfunction "2_2") (pintype "passive"))
      (node (ref "C35") (pin "2") (pinfunction "2_2") (pintype "passive"))
      (node (ref "C5") (pin "2") (pinfunction "2_2") (pintype "passive"))
      (node (ref "C6") (pin "2") (pinfunction "2_2") (pintype "passive"))
      (node (ref "C7") (pin "2") (pinfunction "2_2") (pintype "passive"))
      (node (ref "C8") (pin "2") (pinfunction "2_2") (pintype "passive"))
      (node (ref "D1") (pin "1") (pinfunction "1_1") (pintype "passive"))
      (node (ref "D1") (pin "2") (pinfunction "2_2") (pintype "passive"))
      (node (ref "D11") (pin "3") (pintype "passive"))
      (node (ref "D12") (pin "3") (pintype "passive"))
      (node (ref "D2") (pin "1") (pinfunction "1_1") (pintype "passive"))
      (node (ref "D2") (pin "2") (pinfunction "2_2") (pintype "passive"))
      (node (ref "D5") (pin "3") (pinfunction "GND_3") (pintype "passive"))
      (node (ref "D6") (pin "1") (pinfunction "Cathode_1") (pintype "passive"))
      (node (ref "D7") (pin "1") (pinfunction "Cathode_1") (pintype "passive"))
      (node (ref "D8") (pin "1") (pinfunction "Cathode_1") (pintype "passive"))
      (node (ref "J10") (pin "GND") (pinfunction "GND_GND") (pintype "passive"))
      (node (ref "R11") (pin "2") (pinfunction "2_2") (pintype "passive"))
      (node (ref "R2") (pin "2") (pinfunction "2_2") (pintype "passive"))
      (node (ref "R7") (pin "2") (pinfunction "2_2") (pintype "passive"))
      (node (ref "S1") (pin "3") (pinfunction "3_3") (pintype "passive"))
      (node (ref "U1") (pin "4") (pinfunction "V-_4") (pintype "passive"))
      (node (ref "U2") (pin "4") (pinfunction "GND1_4") (pintype "passive"))
      (node (ref "U3") (pin "19") (pinfunction "VSS_19") (pintype "passive"))
      (node (ref "U3") (pin "7") (pinfunction "RA5/AN4_7") (pintype "passive"))
      (node (ref "U3") (pin "8") (pinfunction "VSS_8") (pintype "passive"))
      (node (ref "U5") (pin "4") (pinfunction "GND1_4") (pintype "passive"))
      (node (ref "U7") (pin "1") (pinfunction "GND_1") (pintype "passive"))
      (node (ref "U7") (pin "2") (pinfunction "GND_2") (pintype "passive"))
    )
    (net (code "28") (name "Net-(C2-Pad1)") (class "Default")
      (node (ref "C2") (pin "1") (pinfunction "1_1") (pintype "passive"))
      (node (ref "C3") (pin "1") (pinfunction "1_1") (pintype "passive"))
      (node (ref "C4") (pin "1") (pinfunction "1_1") (pintype "passive"))
      (node (ref "F1") (pin "2") (pinfunction "2_2") (pintype "passive"))
      (node (ref "L1") (pin "1") (pinfunction "1_1") (pintype "passive"))
      (node (ref "L1") (pin "2") (pinfunction "2_2") (pintype "passive"))
    )
    (net (code "29") (name "Net-(C6-Pad1)") (class "Default")
      (node (ref "C6") (pin "1") (pinfunction "1_1") (pintype "passive"))
      (node (ref "R11") (pin "1") (pinfunction "1_1") (pintype "passive"))
      (node (ref "R4") (pin "2") (pinfunction "2_2") (pintype "passive"))
      (node (ref "X6") (pin "2") (pinfunction "2_2") (pintype "passive"))
    )
    (net (code "30") (name "Net-(C11-Pad1)") (class "Default")
      (node (ref "C11") (pin "1") (pinfunction "1_1") (pintype "passive"))
      (node (ref "R12") (pin "2") (pinfunction "2_2") (pintype "passive"))
    )
    (net (code "31") (name "Net-(C12-Pad1)") (class "Default")
      (node (ref "C12") (pin "1") (pinfunction "1_1") (pintype "passive"))
      (node (ref "D2") (pin "K") (pinfunction "K_K") (pintype "passive"))
      (node (ref "L1") (pin "5") (pinfunction "5_5") (pintype "passive"))
      (node (ref "L1") (pin "6") (pinfunction "6_6") (pintype "passive"))
    )
    (net (code "32") (name "Net-(D1-PadK)") (class "Default")
      (node (ref "D1") (pin "K") (pinfunction "K_K") (pintype "passive"))
      (node (ref "L1") (pin "3") (pinfunction "3_3") (pintype "passive"))
      (node (ref "L1") (pin "4") (pinfunction "4_4") (pintype "passive"))
      (node (ref "L2") (pin "1") (pinfunction "1_1") (pintype "passive"))
      (node (ref "R12") (pin "1") (pinfunction "1_1") (pintype "passive"))
    )
    (net (code "33") (name "Net-(D5-VIN)") (class "Default")
      (node (ref "C25") (pin "1") (pinfunction "1_1") (pintype "passive"))
      (node (ref "D5") (pin "1") (pinfunction "VIN_1") (pintype "passive"))
      (node (ref "X3") (pin "1") (pinfunction "1_1") (pintype "passive"))
    )
    (net (code "34") (name "Net-(D6-Anode)") (class "Default")
      (node (ref "D6") (pin "2") (pinfunction "Anode_2") (pintype "passive"))
      (node (ref "R20") (pin "2") (pinfunction "2_2") (pintype "passive"))
    )
    (net (code "35") (name "Net-(D7-Anode)") (class "Default")
      (node (ref "D7") (pin "2") (pinfunction "Anode_2") (pintype "passive"))
      (node (ref "R22") (pin "2") (pinfunction "2_2") (pintype "passive"))
    )
    (net (code "36") (name "Net-(D8-Anode)") (class "Default")
      (node (ref "D8") (pin "2") (pinfunction "Anode_2") (pintype "passive"))
      (node (ref "R24") (pin "2") (pinfunction "2_2") (pintype "passive"))
    )
    (net (code "37") (name "Net-(D12-Pad1)") (class "Default")
      (node (ref "D12") (pin "1") (pintype "passive"))
      (node (ref "D12") (pin "2") (pintype "passive"))
      (node (ref "F2") (pin "2") (pinfunction "2_2") (pintype "passive"))
      (node (ref "X8") (pin "1") (pinfunction "1_1") (pintype "passive"))
    )
    (net (code "38") (name "Net-(J6-Pad1)") (class "Default")
      (node (ref "J6") (pin "1") (pinfunction "1_1") (pintype "passive"))
      (node (ref "X2") (pin "1") (pinfunction "1_1") (pintype "passive"))
    )
    (net (code "39") (name "Net-(J6-Pad2)") (class "Default")
      (node (ref "J6") (pin "2") (pinfunction "2_2") (pintype "passive"))
      (node (ref "X6") (pin "1") (pinfunction "1_1") (pintype "passive"))
    )
    (net (code "40") (name "Net-(Q1-GATE)") (class "Default")
      (node (ref "C13") (pin "2") (pinfunction "2_2") (pintype "passive"))
      (node (ref "Q1") (pin "1") (pinfunction "GATE_1") (pintype "passive"))
      (node (ref "R1") (pin "1") (pinfunction "1_1") (pintype "passive"))
      (node (ref "R16") (pin "1") (pinfunction "1_1") (pintype "passive"))
      (node (ref "R6") (pin "1") (pinfunction "1_1") (pintype "passive"))
    )
    (net (code "41") (name "Net-(Q2-DRAIN)") (class "Default")
      (node (ref "F2") (pin "1") (pinfunction "1_1") (pintype "passive"))
      (node (ref "Q2") (pin "3") (pinfunction "DRAIN_3") (pintype "passive"))
    )
    (net (code "42") (name "Net-(Q2-GATE)") (class "Default")
      (node (ref "Q2") (pin "1") (pinfunction "GATE_1") (pintype "passive"))
      (node (ref "Q6") (pin "1") (pinfunction "GATE_1") (pintype "passive"))
      (node (ref "R13") (pin "2") (pinfunction "2_2") (pintype "passive"))
      (node (ref "R21") (pin "1") (pinfunction "1_1") (pintype "passive"))
    )
    (net (code "43") (name "Net-(Q2-SOURCE)") (class "Default")
      (node (ref "B1") (pin "1") (pinfunction "1_1") (pintype "passive"))
      (node (ref "Q2") (pin "2") (pinfunction "SOURCE_2") (pintype "passive"))
      (node (ref "Q6") (pin "2") (pinfunction "SOURCE_2") (pintype "passive"))
      (node (ref "R13") (pin "1") (pinfunction "1_1") (pintype "passive"))
    )
    (net (code "44") (name "Net-(Q6-DRAIN)") (class "Default")
      (node (ref "F3") (pin "2") (pinfunction "2_2") (pintype "passive"))
      (node (ref "Q6") (pin "3") (pinfunction "DRAIN_3") (pintype "passive"))
    )
    (net (code "45") (name "Net-(R6-Pad2)") (class "Default")
      (node (ref "R6") (pin "2") (pinfunction "2_2") (pintype "passive"))
      (node (ref "U4") (pin "7") (pinfunction "OUT_7") (pintype "passive"))
    )
    (net (code "46") (name "Net-(R16-Pad2)") (class "Default")
      (node (ref "R16") (pin "2") (pinfunction "2_2") (pintype "passive"))
      (node (ref "U4") (pin "6") (pinfunction "OUT_6") (pintype "passive"))
    )
    (net (code "47") (name "Net-(R21-Pad2)") (class "Default")
      (node (ref "R21") (pin "2") (pinfunction "2_2") (pintype "passive"))
      (node (ref "S1") (pin "4") (pinfunction "4_4") (pintype "passive"))
    )
    (net (code "48") (name "Net-(R26-Pad1)") (class "Default")
      (node (ref "R26") (pin "1") (pinfunction "1_1") (pintype "passive"))
      (node (ref "S1") (pin "1") (pinfunction "1_1") (pintype "passive"))
    )
    (net (code "49") (name "Net-(R26-Pad2)") (class "Default")
      (node (ref "R26") (pin "2") (pinfunction "2_2") (pintype "passive"))
      (node (ref "X4") (pin "1") (pinfunction "1_1") (pintype "passive"))
    )
    (net (code "50") (name "Net-(U1A-+)") (class "Default")
      (node (ref "C7") (pin "1") (pinfunction "1_1") (pintype "passive"))
      (node (ref "R4") (pin "1") (pinfunction "1_1") (pintype "passive"))
      (node (ref "U1") (pin "3") (pinfunction "+_3") (pintype "passive"))
    )
    (net (code "51") (name "Net-(U1A-V+)") (class "Default")
      (node (ref "C1") (pin "1") (pinfunction "1_1") (pintype "passive"))
      (node (ref "U1") (pin "8") (pinfunction "V+_8") (pintype "passive"))
      (node (ref "X1") (pin "2") (pinfunction "2_2") (pintype "passive"))
    )
    (net (code "52") (name "Net-(U1B-+)") (class "Default")
      (node (ref "C16") (pin "1") (pinfunction "1_1") (pintype "passive"))
      (node (ref "R14") (pin "2") (pinfunction "2_2") (pintype "passive"))
      (node (ref "R7") (pin "1") (pinfunction "1_1") (pintype "passive"))
      (node (ref "U1") (pin "5") (pinfunction "+_5") (pintype "passive"))
    )
    (net (code "53") (name "Net-(U1B--)") (class "Default")
      (node (ref "R15") (pin "2") (pinfunction "2_2") (pintype "passive"))
      (node (ref "U1") (pin "6") (pinfunction "-_6") (pintype "passive"))
      (node (ref "U1") (pin "7") (pinfunction "Vo_7") (pintype "passive"))
    )
    (net (code "54") (name "Net-(U2-RX1)") (class "Default")
      (node (ref "U2") (pin "6") (pinfunction "RX1_6") (pintype "passive"))
      (node (ref "U4") (pin "2") (pinfunction "IN_2") (pintype "passive"))
    )
    (net (code "55") (name "Net-(U3-VDDCORE{slash}VCAP)") (class "Default")
      (node (ref "C20") (pin "1") (pinfunction "1_1") (pintype "passive"))
      (node (ref "U3") (pin "6") (pinfunction "VDDCORE/VCAP_6") (pintype "passive"))
    )
    (net (code "56") (name "Net-(U5-RX2)") (class "Default")
      (node (ref "U5") (pin "7") (pinfunction "RX2_7") (pintype "passive"))
      (node (ref "U6") (pin "1") (pinfunction "TXD_1") (pintype "passive"))
    )
    (net (code "57") (name "Net-(U5-TX2)") (class "Default")
      (node (ref "U5") (pin "6") (pinfunction "TX2_6") (pintype "passive"))
      (node (ref "U6") (pin "4") (pinfunction "RXD_4") (pintype "passive"))
    )
    (net (code "58") (name "Net-(U6-RS)") (class "Default")
      (node (ref "R9") (pin "2") (pinfunction "2_2") (pintype "passive"))
      (node (ref "U6") (pin "8") (pinfunction "RS_8") (pintype "passive"))
    )
    (net (code "59") (name "Net-(U7-RS-)") (class "Default")
      (node (ref "D11") (pin "1") (pintype "passive"))
      (node (ref "D11") (pin "2") (pintype "passive"))
      (node (ref "F3") (pin "1") (pinfunction "1_1") (pintype "passive"))
      (node (ref "R27") (pin "2") (pinfunction "2_2") (pintype "passive"))
      (node (ref "U7") (pin "4") (pinfunction "RS-_4") (pintype "passive"))
    )
    (net (code "60") (name "PGND") (class "Default")
      (node (ref "C13") (pin "1") (pinfunction "1_1") (pintype "passive"))
      (node (ref "C15") (pin "2") (pinfunction "2_2") (pintype "passive"))
      (node (ref "C17") (pin "2") (pinfunction "2_2") (pintype "passive"))
      (node (ref "C2") (pin "2") (pinfunction "2_2") (pintype "passive"))
      (node (ref "C3") (pin "2") (pinfunction "2_2") (pintype "passive"))
      (node (ref "C4") (pin "2") (pinfunction "2_2") (pintype "passive"))
      (node (ref "J1") (pin "1") (pinfunction "1_1") (pintype "passive"))
      (node (ref "J1") (pin "2") (pinfunction "2_2") (pintype "passive"))
      (node (ref "Q1") (pin "3") (pinfunction "SOURCE_3") (pintype "passive"))
      (node (ref "R1") (pin "2") (pinfunction "2_2") (pintype "passive"))
      (node (ref "U2") (pin "5") (pinfunction "GND2_5") (pintype "passive"))
      (node (ref "U2") (pin "7") (pinfunction "GND2_7") (pintype "passive"))
      (node (ref "U4") (pin "4") (pinfunction "GND_4") (pintype "passive"))
      (node (ref "U4") (pin "5") (pinfunction "GND_5") (pintype "passive"))
    )
    (net (code "61") (name "VCC") (class "Default")
      (node (ref "C22") (pin "1") (pinfunction "1_1") (pintype "passive"))
      (node (ref "C27") (pin "1") (pinfunction "1_1") (pintype "passive"))
      (node (ref "C31") (pin "1") (pinfunction "1_1") (pintype "passive"))
      (node (ref "C32") (pin "1") (pinfunction "1_1") (pintype "passive"))
      (node (ref "C34") (pin "1") (pinfunction "1_1") (pintype "passive"))
      (node (ref "C35") (pin "1") (pinfunction "1_1") (pintype "passive"))
      (node (ref "J10") (pin "+5") (pinfunction "+5_+5") (pintype "passive"))
      (node (ref "Q3") (pin "2") (pinfunction "SOURCE_2") (pintype "passive"))
      (node (ref "R14") (pin "1") (pinfunction "1_1") (pintype "passive"))
      (node (ref "R25") (pin "1") (pinfunction "1_1") (pintype "passive"))
      (node (ref "R8") (pin "1") (pinfunction "1_1") (pintype "passive"))
      (node (ref "U3") (pin "20") (pinfunction "VDD_20") (pintype "passive"))
      (node (ref "U5") (pin "1") (pinfunction "VDD1_1") (pintype "passive"))
      (node (ref "X1") (pin "1") (pinfunction "1_1") (pintype "passive"))
      (node (ref "X3") (pin "2") (pinfunction "2_2") (pintype "passive"))
      (node (ref "X8") (pin "2") (pinfunction "2_2") (pintype "passive"))
    )
    (net (code "62") (name "VCC_EQL") (class "Default")
      (node (ref "C14") (pin "1") (pinfunction "1_1") (pintype "passive"))
      (node (ref "Q3") (pin "3") (pinfunction "DRAIN_3") (pintype "passive"))
      (node (ref "U2") (pin "1") (pinfunction "VDD1_1") (pintype "passive"))
      (node (ref "U2") (pin "3") (pinfunction "VDD1_3") (pintype "passive"))
    )
    (net (code "63") (name "unconnected-(U3-RB0{slash}AN10{slash}C1INA{slash}FLT0{slash}INT0-Pad21)") (class "Default")
      (node (ref "U3") (pin "21") (pinfunction "RB0/AN10/C1INA/FLT0/INT0_21") (pintype "passive"))
    )
    (net (code "64") (name "unconnected-(U3-RB1{slash}AN8{slash}C1INB{slash}P1B{slash}CTDIN{slash}INT1-Pad22)") (class "Default")
      (node (ref "U3") (pin "22") (pinfunction "RB1/AN8/C1INB/P1B/CTDIN/INT1_22") (pintype "passive"))
    )
    (net (code "65") (name "unconnected-(U3-RB5{slash}T0CKI{slash}T3CKI{slash}CCP5{slash}KBI1-Pad26)") (class "Default")
      (node (ref "U3") (pin "26") (pinfunction "RB5/T0CKI/T3CKI/CCP5/KBI1_26") (pintype "passive"))
    )
    (net (code "66") (name "unconnected-(U3-RC4{slash}SDA{slash}SDI-Pad15)") (class "Default")
      (node (ref "U3") (pin "15") (pinfunction "RC4/SDA/SDI_15") (pintype "passive"))
    )
    (net (code "67") (name "unconnected-(U3-RC5{slash}SDO-Pad16)") (class "Default")
      (node (ref "U3") (pin "16") (pinfunction "RC5/SDO_16") (pintype "passive"))
    )
    (net (code "68") (name "unconnected-(U3-RC6{slash}CANTX{slash}TX1{slash}CK1{slash}CCP3-Pad17)") (class "Default")
      (node (ref "U3") (pin "17") (pinfunction "RC6/CANTX/TX1/CK1/CCP3_17") (pintype "passive"))
    )
    (net (code "69") (name "unconnected-(U3-RC7{slash}CANRX{slash}RX1{slash}DT1{slash}CCP4-Pad18)") (class "Default")
      (node (ref "U3") (pin "18") (pinfunction "RC7/CANRX/RX1/DT1/CCP4_18") (pintype "passive"))
    )
  )
)
